# Sheet3-USB.net
KiCad netlist of a schematic drawn in Altium Designer
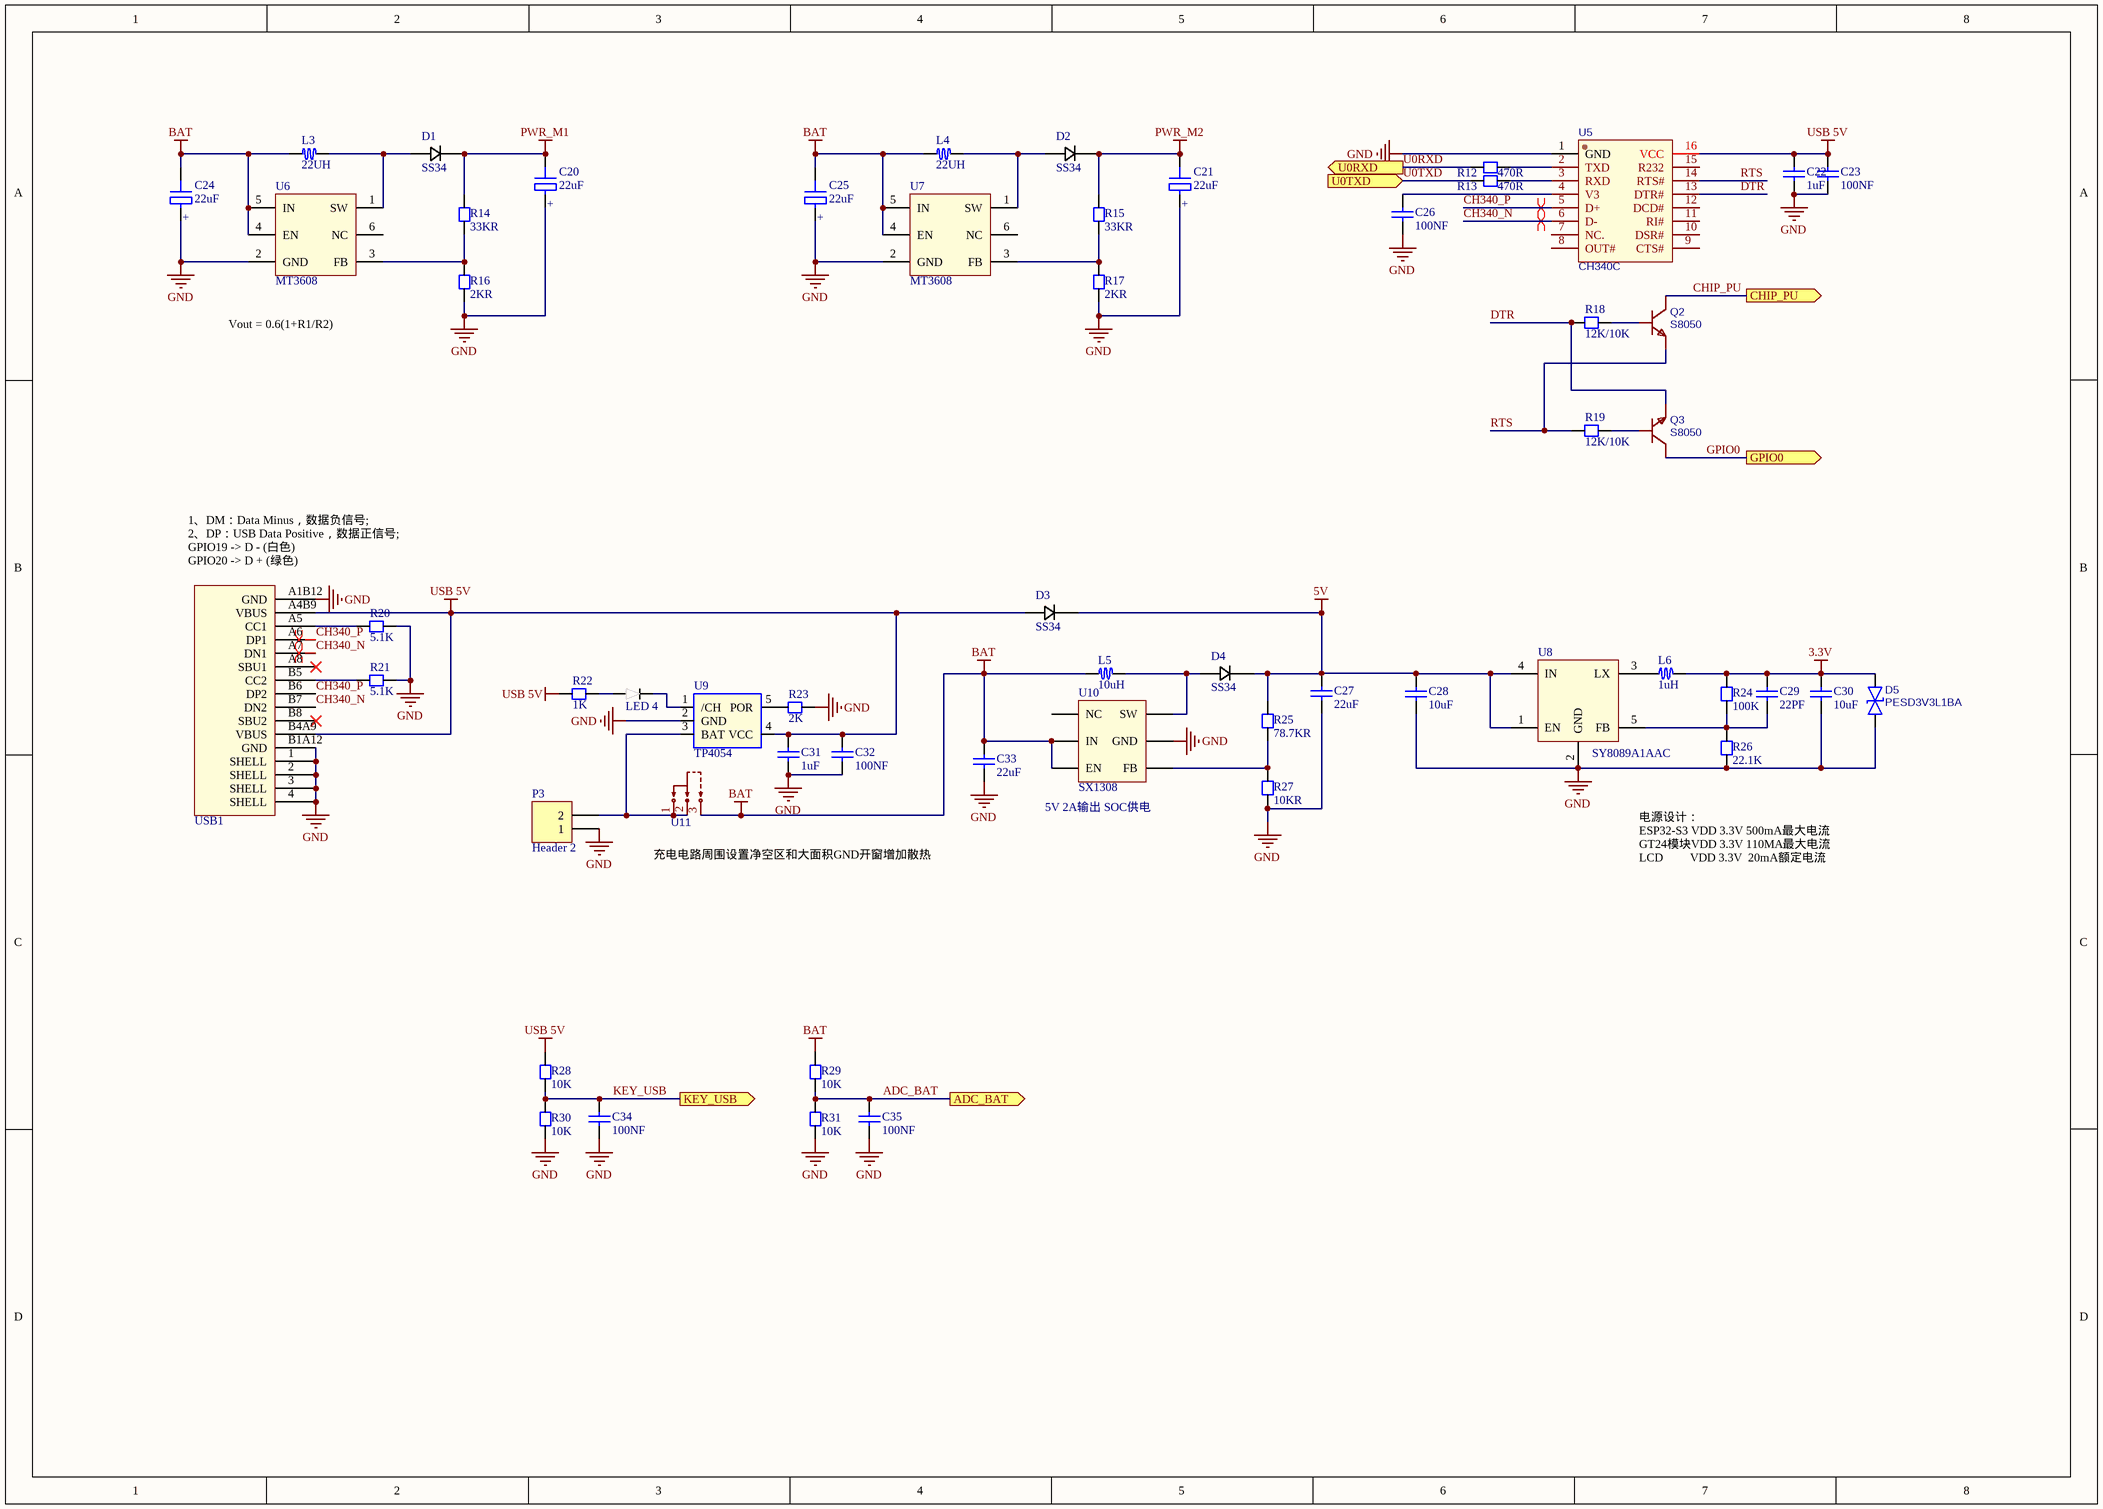
[diagram p0: Sheet3-USB.SchDoc]

(export (version "E")
  (design (tool "Eeschema 10.0.6"))
  (components
    (comp (ref "C20")
      (value "22uF")
      (footprint "TAN-A-1206")
      (description "钽电容")
      (libsource (lib "base") (part "CAP TAN-A-1206"))
    )
    (comp (ref "C21")
      (value "22uF")
      (footprint "TAN-A-1206")
      (description "钽电容")
      (libsource (lib "base") (part "CAP TAN-A-1206"))
    )
    (comp (ref "C22")
      (value "1uF")
      (footprint "CC1608-0603")
      (description "0603封装的电容")
      (fields (field (name "PUBLISHER") "Altium Limited"))
      (libsource (lib "base") (part "Cap Chip 0603"))
    )
    (comp (ref "C23")
      (value "100NF")
      (footprint "CC1608-0603")
      (description "0603封装的电容")
      (fields (field (name "PUBLISHER") "Altium Limited"))
      (libsource (lib "base") (part "Cap Chip 0603"))
    )
    (comp (ref "C24")
      (value "22uF")
      (footprint "TAN-A-1206")
      (description "钽电容")
      (libsource (lib "base") (part "CAP TAN-A-1206"))
    )
    (comp (ref "C25")
      (value "22uF")
      (footprint "TAN-A-1206")
      (description "钽电容")
      (libsource (lib "base") (part "CAP TAN-A-1206"))
    )
    (comp (ref "C26")
      (value "100NF")
      (footprint "CC1608-0603")
      (description "0603封装的电容")
      (fields (field (name "PUBLISHER") "Altium Limited"))
      (libsource (lib "base") (part "Cap Chip 0603"))
    )
    (comp (ref "C27")
      (value "22uF")
      (footprint "CC1608-0603")
      (description "贴片电容")
      (libsource (lib "tianxiaohua_Schlib") (part "Chip capacitor"))
    )
    (comp (ref "C28")
      (value "10uF")
      (footprint "CC1608-0603")
      (description "0603封装的电容")
      (fields (field (name "PUBLISHER") "Altium Limited"))
      (libsource (lib "base") (part "Cap Chip 0603"))
    )
    (comp (ref "C29")
      (value "22PF")
      (footprint "CC1608-0603")
      (description "0603封装的电容")
      (fields (field (name "PUBLISHER") "Altium Limited"))
      (libsource (lib "base") (part "Cap Chip 0603"))
    )
    (comp (ref "C30")
      (value "10uF")
      (footprint "CC1608-0603")
      (description "0603封装的电容")
      (fields (field (name "PUBLISHER") "Altium Limited"))
      (libsource (lib "base") (part "Cap Chip 0603"))
    )
    (comp (ref "C31")
      (value "1uF")
      (footprint "CC1608-0603")
      (description "0603封装的电容")
      (fields (field (name "PUBLISHER") "Altium Limited"))
      (libsource (lib "base") (part "Cap Chip 0603"))
    )
    (comp (ref "C32")
      (value "100NF")
      (footprint "CC1608-0603")
      (description "0603封装的电容")
      (fields (field (name "PUBLISHER") "Altium Limited"))
      (libsource (lib "base") (part "Cap Chip 0603"))
    )
    (comp (ref "C33")
      (value "22uF")
      (footprint "CC1608-0603")
      (description "0603封装的电容")
      (fields (field (name "PUBLISHER") "Altium Limited"))
      (libsource (lib "base") (part "Cap Chip 0603"))
    )
    (comp (ref "C34")
      (value "100NF")
      (footprint "CC1608-0603")
      (description "0603封装的电容")
      (fields (field (name "PUBLISHER") "Altium Limited"))
      (libsource (lib "base") (part "Cap Chip 0603"))
    )
    (comp (ref "C35")
      (value "100NF")
      (footprint "CC1608-0603")
      (description "0603封装的电容")
      (fields (field (name "PUBLISHER") "Altium Limited"))
      (libsource (lib "base") (part "Cap Chip 0603"))
    )
    (comp (ref "D1")
      (value "SS34")
      (footprint "DO-214 AA")
      (description "肖特基二极管")
      (libsource (lib "transistor") (part "SS34"))
    )
    (comp (ref "D2")
      (value "SS34")
      (footprint "DO-214 AA")
      (description "肖特基二极管")
      (libsource (lib "transistor") (part "SS34"))
    )
    (comp (ref "D3")
      (value "SS34")
      (footprint "DO-214 AA")
      (description "肖特基二极管")
      (libsource (lib "transistor") (part "SS34"))
    )
    (comp (ref "D4")
      (value "SS34")
      (footprint "DO-214 AA")
      (description "肖特基二极管")
      (libsource (lib "transistor") (part "SS34"))
    )
    (comp (ref "D5")
      (value "PESD3V3L1BA")
      (footprint "SOD-323")
      (description "SOD-323 3.3V 双向ESD防静电二极管保护芯片")
      (fields (field (name "MANUFACTURER") "MDD") (field (name "MANUFACTURER PART") "SMAJ6.5CA"))
      (libsource (lib "transistor") (part "PESD3V3L1BA"))
    )
    (comp (ref "L3")
      (value "22UH")
      (footprint "CDRH104R")
      (description "贴片电感 CDRH104R 封装")
      (libsource (lib "base") (part "Inductor-CDRH104R"))
    )
    (comp (ref "L4")
      (value "22UH")
      (footprint "CDRH104R")
      (description "贴片电感 CDRH104R 封装")
      (libsource (lib "base") (part "Inductor-CDRH104R"))
    )
    (comp (ref "L5")
      (value "10uH")
      (footprint "Inductor-6045")
      (description "6045封装 线绕SMD功率电感")
      (libsource (lib "base") (part "Inductor-6045"))
    )
    (comp (ref "L6")
      (value "1uH")
      (footprint "Inductor-4018")
      (description "贴片电感 1206封装")
      (libsource (lib "base") (part "Inductor-4018"))
    )
    (comp (ref "LED 4") (value "LED 0603") (footprint "LED 0603") (libsource (lib "base") (part "LED 0603")))
    (comp (ref "P3")
      (value "Header 2")
      (footprint "HX2.54-2")
      (description "Header, 2-Pin")
      (fields (field (name "PUBLISHER") "Altium Limited"))
      (libsource (lib "Connectors") (part "Header 2"))
    )
    (comp (ref "Q2")
      (value "S8050")
      (footprint "SOT-23")
      (fields (field (name "MANUFACTURER") "SALLTECH(萨瑞)") (field (name "CONTRIBUTOR") "lcsc"))
      (libsource (lib "transistor") (part "S8050"))
    )
    (comp (ref "Q3")
      (value "S8050")
      (footprint "SOT-23")
      (fields (field (name "MANUFACTURER") "SALLTECH(萨瑞)") (field (name "CONTRIBUTOR") "lcsc"))
      (libsource (lib "transistor") (part "S8050"))
    )
    (comp (ref "R12")
      (value "470R")
      (footprint "CR1608-0603")
      (description "0603封装电阻")
      (fields (field (name "PUBLISHER") "Altium Limited"))
      (libsource (lib "") (part "Resistor Chip 0603_1"))
    )
    (comp (ref "R13")
      (value "470R")
      (footprint "CR1608-0603")
      (description "0603封装电阻")
      (fields (field (name "PUBLISHER") "Altium Limited"))
      (libsource (lib "") (part "Resistor Chip 0603_1"))
    )
    (comp (ref "R14")
      (value "33KR")
      (footprint "CR1608-0603")
      (description "贴片电阻")
      (libsource (lib "tianxiaohua_Schlib") (part "Chip resistor"))
    )
    (comp (ref "R15")
      (value "33KR")
      (footprint "CR1608-0603")
      (description "贴片电阻")
      (libsource (lib "tianxiaohua_Schlib") (part "Chip resistor"))
    )
    (comp (ref "R16")
      (value "2KR")
      (footprint "CR1608-0603")
      (description "贴片电阻")
      (libsource (lib "tianxiaohua_Schlib") (part "Chip resistor"))
    )
    (comp (ref "R17")
      (value "2KR")
      (footprint "CR1608-0603")
      (description "贴片电阻")
      (libsource (lib "tianxiaohua_Schlib") (part "Chip resistor"))
    )
    (comp (ref "R18")
      (value "12K/10K")
      (footprint "CR1608-0603")
      (description "0603封装电阻")
      (fields (field (name "PUBLISHER") "Altium Limited"))
      (libsource (lib "") (part "Resistor Chip 0603_2"))
    )
    (comp (ref "R19")
      (value "12K/10K")
      (footprint "CR1608-0603")
      (description "0603封装电阻")
      (fields (field (name "PUBLISHER") "Altium Limited"))
      (libsource (lib "base") (part "Resistor Chip 0603"))
    )
    (comp (ref "R20")
      (value "5.1K")
      (footprint "CR1608-0603")
      (description "0603封装电阻")
      (fields (field (name "PUBLISHER") "Altium Limited"))
      (libsource (lib "") (part "Resistor Chip 0603_1"))
    )
    (comp (ref "R21")
      (value "5.1K")
      (footprint "CR1608-0603")
      (description "0603封装电阻")
      (fields (field (name "PUBLISHER") "Altium Limited"))
      (libsource (lib "") (part "Resistor Chip 0603_1"))
    )
    (comp (ref "R22")
      (value "1K")
      (footprint "CR1608-0603")
      (description "0603封装电阻")
      (fields (field (name "PUBLISHER") "Altium Limited"))
      (libsource (lib "") (part "Resistor Chip 0603_2"))
    )
    (comp (ref "R23")
      (value "2K")
      (footprint "CR1608-0603")
      (description "0603封装电阻")
      (fields (field (name "PUBLISHER") "Altium Limited"))
      (libsource (lib "") (part "Resistor Chip 0603_2"))
    )
    (comp (ref "R24")
      (value "100K")
      (footprint "CR1608-0603")
      (description "0603封装电阻")
      (fields (field (name "PUBLISHER") "Altium Limited"))
      (libsource (lib "") (part "Resistor Chip 0603_3"))
    )
    (comp (ref "R25")
      (value "78.7KR")
      (footprint "CR1608-0603")
      (description "贴片电阻")
      (libsource (lib "") (part "Chip resistor_1"))
    )
    (comp (ref "R26")
      (value "22.1K")
      (footprint "CR1608-0603")
      (description "0603封装电阻")
      (fields (field (name "PUBLISHER") "Altium Limited"))
      (libsource (lib "") (part "Resistor Chip 0603_3"))
    )
    (comp (ref "R27")
      (value "10KR")
      (footprint "CR1608-0603")
      (description "贴片电阻")
      (libsource (lib "") (part "Chip resistor_1"))
    )
    (comp (ref "R28")
      (value "10K")
      (footprint "CR1608-0603")
      (description "0603封装电阻")
      (fields (field (name "PUBLISHER") "Altium Limited"))
      (libsource (lib "base") (part "Resistor Chip 0603"))
    )
    (comp (ref "R29")
      (value "10K")
      (footprint "CR1608-0603")
      (description "0603封装电阻")
      (fields (field (name "PUBLISHER") "Altium Limited"))
      (libsource (lib "base") (part "Resistor Chip 0603"))
    )
    (comp (ref "R30")
      (value "10K")
      (footprint "CR1608-0603")
      (description "0603封装电阻")
      (fields (field (name "PUBLISHER") "Altium Limited"))
      (libsource (lib "base") (part "Resistor Chip 0603"))
    )
    (comp (ref "R31")
      (value "10K")
      (footprint "CR1608-0603")
      (description "0603封装电阻")
      (fields (field (name "PUBLISHER") "Altium Limited"))
      (libsource (lib "base") (part "Resistor Chip 0603"))
    )
    (comp (ref "U5")
      (value "CH340C")
      (footprint "SOP-16")
      (fields (field (name "MANUFACTURER") "WCH(南京沁恒)"))
      (libsource (lib "PB-Chip") (part "CH340C"))
    )
    (comp (ref "U6") (value "MT3608") (footprint "SOT23-6") (libsource (lib "power-chip") (part "MT3608")))
    (comp (ref "U7") (value "MT3608") (footprint "SOT23-6") (libsource (lib "power-chip") (part "MT3608")))
    (comp (ref "U8")
      (value "SY8089A1AAC")
      (footprint "SOT23-5")
      (libsource (lib "power-chip") (part "SY8089A1AAC"))
    )
    (comp (ref "U9")
      (value "TP4054")
      (footprint "SOT23-5")
      (description "迷你充电IC SOT-23-5")
      (libsource (lib "power-chip") (part "TP4054"))
    )
    (comp (ref "U10")
      (value "SX1308")
      (footprint "SOT23-6")
      (description "SOT23-6 升压芯片")
      (libsource (lib "power-chip") (part "SX1308"))
    )
    (comp (ref "U11")
      (value "HX SS12D10G4")
      (footprint "SW-TH_3P-SS12D06")
      (fields (field (name "BOM_SUPPLIER PART") "C5149841") (field (name "CONTRIBUTOR") "lcsc"))
      (libsource (lib "base") (part "SW-TH_3P-SS12D06"))
    )
    (comp (ref "USB1")
      (value "Tpye-c 16P")
      (footprint "TYPE-C 16P")
      (description "16P 封装的TYPE -c接口 4固定插脚 双向")
      (libsource (lib "Connectors") (part "Tpye-c 16P"))
    )
  )
  (nets
    (net (code "1") (name "/ADC_BAT") (class "Default")
      (node (ref "C35") (pin "2") (pinfunction "2_2") (pintype "passive"))
      (node (ref "R29") (pin "1") (pinfunction "1_1") (pintype "passive"))
      (node (ref "R31") (pin "2") (pinfunction "2_2") (pintype "passive"))
    )
    (net (code "2") (name "/CH340_N") (class "Default")
      (node (ref "U5") (pin "6") (pinfunction "D-_6") (pintype "passive"))
      (node (ref "USB1") (pin "A7") (pinfunction "DN1_A7") (pintype "power_in"))
      (node (ref "USB1") (pin "B7") (pinfunction "DN2_B7") (pintype "power_in"))
    )
    (net (code "3") (name "/CH340_P") (class "Default")
      (node (ref "U5") (pin "5") (pinfunction "D+_5") (pintype "passive"))
      (node (ref "USB1") (pin "A6") (pinfunction "DP1_A6") (pintype "power_in"))
      (node (ref "USB1") (pin "B6") (pinfunction "DP2_B6") (pintype "power_in"))
    )
    (net (code "4") (name "/CHIP_PU") (class "Default")
      (node (ref "Q2") (pin "3") (pinfunction "C_3") (pintype "passive"))
    )
    (net (code "5") (name "/DTR") (class "Default")
      (node (ref "Q3") (pin "2") (pinfunction "E_2") (pintype "passive"))
      (node (ref "R18") (pin "1") (pinfunction "1_1") (pintype "passive"))
      (node (ref "U5") (pin "13") (pinfunction "DTR#_13") (pintype "passive"))
    )
    (net (code "6") (name "/GPIO0") (class "Default")
      (node (ref "Q3") (pin "3") (pinfunction "C_3") (pintype "passive"))
    )
    (net (code "7") (name "/KEY_USB") (class "Default")
      (node (ref "C34") (pin "2") (pinfunction "2_2") (pintype "passive"))
      (node (ref "R28") (pin "1") (pinfunction "1_1") (pintype "passive"))
      (node (ref "R30") (pin "2") (pinfunction "2_2") (pintype "passive"))
    )
    (net (code "8") (name "/RTS") (class "Default")
      (node (ref "Q2") (pin "2") (pinfunction "E_2") (pintype "passive"))
      (node (ref "R19") (pin "1") (pinfunction "1_1") (pintype "passive"))
      (node (ref "U5") (pin "14") (pinfunction "RTS#_14") (pintype "passive"))
    )
    (net (code "9") (name "/U0RXD") (class "Default")
      (node (ref "R12") (pin "2") (pinfunction "2_2") (pintype "passive"))
    )
    (net (code "10") (name "/U0TXD") (class "Default")
      (node (ref "R13") (pin "2") (pinfunction "2_2") (pintype "passive"))
    )
    (net (code "11") (name "3.3V") (class "Default")
      (node (ref "C29") (pin "2") (pinfunction "2_2") (pintype "passive"))
      (node (ref "C30") (pin "2") (pinfunction "2_2") (pintype "passive"))
      (node (ref "D5") (pin "1") (pinfunction "1_1") (pintype "passive"))
      (node (ref "L6") (pin "2") (pinfunction "2_2") (pintype "passive"))
      (node (ref "R24") (pin "1") (pinfunction "1_1") (pintype "passive"))
    )
    (net (code "12") (name "5V") (class "Default")
      (node (ref "C27") (pin "1") (pinfunction "1_1") (pintype "passive"))
      (node (ref "C28") (pin "2") (pinfunction "2_2") (pintype "passive"))
      (node (ref "D3") (pin "1") (pinfunction "K_1") (pintype "passive"))
      (node (ref "D4") (pin "1") (pinfunction "K_1") (pintype "passive"))
      (node (ref "R25") (pin "2") (pinfunction "2_2") (pintype "passive"))
      (node (ref "U8") (pin "1") (pinfunction "EN_1") (pintype "passive"))
      (node (ref "U8") (pin "4") (pinfunction "IN_4") (pintype "passive"))
    )
    (net (code "13") (name "BAT") (class "Default")
      (node (ref "C24") (pin "2") (pinfunction "-_2") (pintype "passive"))
      (node (ref "C25") (pin "2") (pinfunction "-_2") (pintype "passive"))
      (node (ref "C33") (pin "2") (pinfunction "2_2") (pintype "passive"))
      (node (ref "L3") (pin "1") (pinfunction "1_1") (pintype "passive"))
      (node (ref "L4") (pin "1") (pinfunction "1_1") (pintype "passive"))
      (node (ref "L5") (pin "1") (pinfunction "1_1") (pintype "passive"))
      (node (ref "R29") (pin "2") (pinfunction "2_2") (pintype "passive"))
      (node (ref "U10") (pin "4") (pinfunction "EN_4") (pintype "passive"))
      (node (ref "U10") (pin "5") (pinfunction "IN_5") (pintype "passive"))
      (node (ref "U11") (pin "3") (pinfunction "3_3") (pintype "passive"))
      (node (ref "U6") (pin "4") (pinfunction "EN_4") (pintype "passive"))
      (node (ref "U6") (pin "5") (pinfunction "IN_5") (pintype "passive"))
      (node (ref "U7") (pin "4") (pinfunction "EN_4") (pintype "passive"))
      (node (ref "U7") (pin "5") (pinfunction "IN_5") (pintype "passive"))
    )
    (net (code "14") (name "GND") (class "Default")
      (node (ref "C20") (pin "1") (pinfunction "+_1") (pintype "passive"))
      (node (ref "C21") (pin "1") (pinfunction "+_1") (pintype "passive"))
      (node (ref "C22") (pin "1") (pinfunction "1_1") (pintype "passive"))
      (node (ref "C23") (pin "1") (pinfunction "1_1") (pintype "passive"))
      (node (ref "C24") (pin "1") (pinfunction "+_1") (pintype "passive"))
      (node (ref "C25") (pin "1") (pinfunction "+_1") (pintype "passive"))
      (node (ref "C26") (pin "1") (pinfunction "1_1") (pintype "passive"))
      (node (ref "C27") (pin "2") (pinfunction "2_2") (pintype "passive"))
      (node (ref "C28") (pin "1") (pinfunction "1_1") (pintype "passive"))
      (node (ref "C30") (pin "1") (pinfunction "1_1") (pintype "passive"))
      (node (ref "C31") (pin "1") (pinfunction "1_1") (pintype "passive"))
      (node (ref "C32") (pin "1") (pinfunction "1_1") (pintype "passive"))
      (node (ref "C33") (pin "1") (pinfunction "1_1") (pintype "passive"))
      (node (ref "C34") (pin "1") (pinfunction "1_1") (pintype "passive"))
      (node (ref "C35") (pin "1") (pinfunction "1_1") (pintype "passive"))
      (node (ref "D5") (pin "2") (pinfunction "2_2") (pintype "passive"))
      (node (ref "P3") (pin "1") (pinfunction "1_1") (pintype "passive"))
      (node (ref "R16") (pin "2") (pinfunction "2_2") (pintype "passive"))
      (node (ref "R17") (pin "2") (pinfunction "2_2") (pintype "passive"))
      (node (ref "R20") (pin "1") (pinfunction "1_1") (pintype "passive"))
      (node (ref "R21") (pin "1") (pinfunction "1_1") (pintype "passive"))
      (node (ref "R23") (pin "2") (pinfunction "2_2") (pintype "passive"))
      (node (ref "R26") (pin "2") (pinfunction "2_2") (pintype "passive"))
      (node (ref "R27") (pin "1") (pinfunction "1_1") (pintype "passive"))
      (node (ref "R30") (pin "1") (pinfunction "1_1") (pintype "passive"))
      (node (ref "R31") (pin "1") (pinfunction "1_1") (pintype "passive"))
      (node (ref "U10") (pin "2") (pinfunction "GND_2") (pintype "passive"))
      (node (ref "U5") (pin "1") (pinfunction "GND_1") (pintype "passive"))
      (node (ref "U6") (pin "2") (pinfunction "GND_2") (pintype "passive"))
      (node (ref "U7") (pin "2") (pinfunction "GND_2") (pintype "passive"))
      (node (ref "U8") (pin "2") (pinfunction "GND_2") (pintype "passive"))
      (node (ref "U9") (pin "2") (pinfunction "GND_2") (pintype "passive"))
      (node (ref "USB1") (pin "1") (pinfunction "SHELL_1") (pintype "power_in"))
      (node (ref "USB1") (pin "2") (pinfunction "SHELL_2") (pintype "power_in"))
      (node (ref "USB1") (pin "3") (pinfunction "SHELL_3") (pintype "power_in"))
      (node (ref "USB1") (pin "4") (pinfunction "SHELL_4") (pintype "power_in"))
      (node (ref "USB1") (pin "A1B12") (pinfunction "GND_A1B12") (pintype "power_in"))
      (node (ref "USB1") (pin "B1A12") (pinfunction "GND_B1A12") (pintype "power_in"))
    )
    (net (code "15") (name "Net-(D1-A)") (class "Default")
      (node (ref "D1") (pin "2") (pinfunction "A_2") (pintype "passive"))
      (node (ref "L3") (pin "2") (pinfunction "2_2") (pintype "passive"))
      (node (ref "U6") (pin "1") (pinfunction "SW_1") (pintype "passive"))
    )
    (net (code "16") (name "Net-(D2-A)") (class "Default")
      (node (ref "D2") (pin "2") (pinfunction "A_2") (pintype "passive"))
      (node (ref "L4") (pin "2") (pinfunction "2_2") (pintype "passive"))
      (node (ref "U7") (pin "1") (pinfunction "SW_1") (pintype "passive"))
    )
    (net (code "17") (name "Net-(D4-A)") (class "Default")
      (node (ref "D4") (pin "2") (pinfunction "A_2") (pintype "passive"))
      (node (ref "L5") (pin "2") (pinfunction "2_2") (pintype "passive"))
      (node (ref "U10") (pin "1") (pinfunction "SW_1") (pintype "passive"))
    )
    (net (code "18") (name "Net-(LED 4-Pad1)") (class "Default")
      (node (ref "LED 4") (pin "1") (pinfunction "1_1") (pintype "passive"))
      (node (ref "R22") (pin "2") (pinfunction "2_2") (pintype "passive"))
    )
    (net (code "19") (name "Net-(Q2-B)") (class "Default")
      (node (ref "Q2") (pin "1") (pinfunction "B_1") (pintype "passive"))
      (node (ref "R18") (pin "2") (pinfunction "2_2") (pintype "passive"))
    )
    (net (code "20") (name "Net-(Q3-B)") (class "Default")
      (node (ref "Q3") (pin "1") (pinfunction "B_1") (pintype "passive"))
      (node (ref "R19") (pin "2") (pinfunction "2_2") (pintype "passive"))
    )
    (net (code "21") (name "Net-(U5-RXD)") (class "Default")
      (node (ref "R13") (pin "1") (pinfunction "1_1") (pintype "passive"))
      (node (ref "U5") (pin "3") (pinfunction "RXD_3") (pintype "passive"))
    )
    (net (code "22") (name "Net-(U5-TXD)") (class "Default")
      (node (ref "R12") (pin "1") (pinfunction "1_1") (pintype "passive"))
      (node (ref "U5") (pin "2") (pinfunction "TXD_2") (pintype "passive"))
    )
    (net (code "23") (name "Net-(U5-V3)") (class "Default")
      (node (ref "C26") (pin "2") (pinfunction "2_2") (pintype "passive"))
      (node (ref "U5") (pin "4") (pinfunction "V3_4") (pintype "passive"))
    )
    (net (code "24") (name "Net-(U6-FB)") (class "Default")
      (node (ref "R14") (pin "2") (pinfunction "2_2") (pintype "passive"))
      (node (ref "R16") (pin "1") (pinfunction "1_1") (pintype "passive"))
      (node (ref "U6") (pin "3") (pinfunction "FB_3") (pintype "passive"))
    )
    (net (code "25") (name "Net-(U7-FB)") (class "Default")
      (node (ref "R15") (pin "2") (pinfunction "2_2") (pintype "passive"))
      (node (ref "R17") (pin "1") (pinfunction "1_1") (pintype "passive"))
      (node (ref "U7") (pin "3") (pinfunction "FB_3") (pintype "passive"))
    )
    (net (code "26") (name "Net-(U8-FB)") (class "Default")
      (node (ref "C29") (pin "1") (pinfunction "1_1") (pintype "passive"))
      (node (ref "R24") (pin "2") (pinfunction "2_2") (pintype "passive"))
      (node (ref "R26") (pin "1") (pinfunction "1_1") (pintype "passive"))
      (node (ref "U8") (pin "5") (pinfunction "FB_5") (pintype "passive"))
    )
    (net (code "27") (name "Net-(U8-LX)") (class "Default")
      (node (ref "L6") (pin "1") (pinfunction "1_1") (pintype "passive"))
      (node (ref "U8") (pin "3") (pinfunction "LX_3") (pintype "passive"))
    )
    (net (code "28") (name "Net-(U9-BAT)") (class "Default")
      (node (ref "P3") (pin "2") (pinfunction "2_2") (pintype "passive"))
      (node (ref "U11") (pin "1") (pinfunction "1_1") (pintype "passive"))
      (node (ref "U11") (pin "2") (pinfunction "2_2") (pintype "passive"))
      (node (ref "U9") (pin "3") (pinfunction "BAT_3") (pintype "passive"))
    )
    (net (code "29") (name "Net-(U9-POR)") (class "Default")
      (node (ref "R23") (pin "1") (pinfunction "1_1") (pintype "passive"))
      (node (ref "U9") (pin "5") (pinfunction "POR_5") (pintype "passive"))
    )
    (net (code "30") (name "Net-(U9-{slash}CH)") (class "Default")
      (node (ref "LED 4") (pin "2") (pinfunction "2_2") (pintype "passive"))
      (node (ref "U9") (pin "1") (pinfunction "/CH_1") (pintype "passive"))
    )
    (net (code "31") (name "Net-(U10-FB)") (class "Default")
      (node (ref "R25") (pin "1") (pinfunction "1_1") (pintype "passive"))
      (node (ref "R27") (pin "2") (pinfunction "2_2") (pintype "passive"))
      (node (ref "U10") (pin "3") (pinfunction "FB_3") (pintype "passive"))
    )
    (net (code "32") (name "Net-(USB1-CC1)") (class "Default")
      (node (ref "R20") (pin "2") (pinfunction "2_2") (pintype "passive"))
      (node (ref "USB1") (pin "A5") (pinfunction "CC1_A5") (pintype "power_in"))
    )
    (net (code "33") (name "Net-(USB1-CC2)") (class "Default")
      (node (ref "R21") (pin "2") (pinfunction "2_2") (pintype "passive"))
      (node (ref "USB1") (pin "B5") (pinfunction "CC2_B5") (pintype "power_in"))
    )
    (net (code "34") (name "PWR_M1") (class "Default")
      (node (ref "C20") (pin "2") (pinfunction "-_2") (pintype "passive"))
      (node (ref "D1") (pin "1") (pinfunction "K_1") (pintype "passive"))
      (node (ref "R14") (pin "1") (pinfunction "1_1") (pintype "passive"))
    )
    (net (code "35") (name "PWR_M2") (class "Default")
      (node (ref "C21") (pin "2") (pinfunction "-_2") (pintype "passive"))
      (node (ref "D2") (pin "1") (pinfunction "K_1") (pintype "passive"))
      (node (ref "R15") (pin "1") (pinfunction "1_1") (pintype "passive"))
    )
    (net (code "36") (name "USB 5V") (class "Default")
      (node (ref "C22") (pin "2") (pinfunction "2_2") (pintype "passive"))
      (node (ref "C23") (pin "2") (pinfunction "2_2") (pintype "passive"))
      (node (ref "C31") (pin "2") (pinfunction "2_2") (pintype "passive"))
      (node (ref "C32") (pin "2") (pinfunction "2_2") (pintype "passive"))
      (node (ref "D3") (pin "2") (pinfunction "A_2") (pintype "passive"))
      (node (ref "R22") (pin "1") (pinfunction "1_1") (pintype "passive"))
      (node (ref "R28") (pin "2") (pinfunction "2_2") (pintype "passive"))
      (node (ref "U5") (pin "16") (pinfunction "VCC_16") (pintype "passive"))
      (node (ref "U9") (pin "4") (pinfunction "VCC_4") (pintype "passive"))
      (node (ref "USB1") (pin "A4B9") (pinfunction "VBUS_A4B9") (pintype "power_in"))
      (node (ref "USB1") (pin "B4A9") (pinfunction "VBUS_B4A9") (pintype "power_in"))
    )
    (net (code "37") (name "unconnected-(U5-CTS#-Pad9)") (class "Default")
      (node (ref "U5") (pin "9") (pinfunction "CTS#_9") (pintype "passive"))
    )
    (net (code "38") (name "unconnected-(U5-DCD#-Pad12)") (class "Default")
      (node (ref "U5") (pin "12") (pinfunction "DCD#_12") (pintype "passive"))
    )
    (net (code "39") (name "unconnected-(U5-DSR#-Pad10)") (class "Default")
      (node (ref "U5") (pin "10") (pinfunction "DSR#_10") (pintype "passive"))
    )
    (net (code "40") (name "unconnected-(U5-NC.-Pad7)") (class "Default")
      (node (ref "U5") (pin "7") (pinfunction "NC._7") (pintype "passive"))
    )
    (net (code "41") (name "unconnected-(U5-OUT#-Pad8)") (class "Default")
      (node (ref "U5") (pin "8") (pinfunction "OUT#_8") (pintype "passive"))
    )
    (net (code "42") (name "unconnected-(U5-R232-Pad15)") (class "Default")
      (node (ref "U5") (pin "15") (pinfunction "R232_15") (pintype "passive"))
    )
    (net (code "43") (name "unconnected-(U5-RI#-Pad11)") (class "Default")
      (node (ref "U5") (pin "11") (pinfunction "RI#_11") (pintype "passive"))
    )
    (net (code "44") (name "unconnected-(U6-NC-Pad6)") (class "Default")
      (node (ref "U6") (pin "6") (pinfunction "NC_6") (pintype "passive"))
    )
    (net (code "45") (name "unconnected-(U7-NC-Pad6)") (class "Default")
      (node (ref "U7") (pin "6") (pinfunction "NC_6") (pintype "passive"))
    )
    (net (code "46") (name "unconnected-(U10-NC-Pad6)") (class "Default")
      (node (ref "U10") (pin "6") (pinfunction "NC_6") (pintype "passive"))
    )
    (net (code "47") (name "unconnected-(USB1-SBU1-PadA8)") (class "Default")
      (node (ref "USB1") (pin "A8") (pinfunction "SBU1_A8") (pintype "power_in+no_connect"))
    )
    (net (code "48") (name "unconnected-(USB1-SBU2-PadB8)") (class "Default")
      (node (ref "USB1") (pin "B8") (pinfunction "SBU2_B8") (pintype "power_in+no_connect"))
    )
  )
)
